# Shield.net
KiCad netlist of a schematic drawn in EAGLE
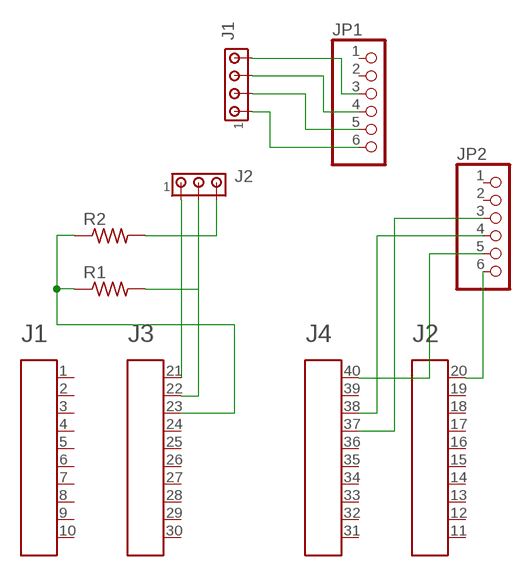
[diagram p0: schematic, sheet 1]

(export (version "E")
  (design (tool "Eeschema 10.0.6"))
  (components
    (comp (ref "A1")
      (value "HEADER4X10-BOOSTERPACK")
      (footprint "eagle-import:4X10-BOOSTERPACK")
      (libsource (lib "eagle-import") (part "HEADER4X10-BOOSTERPACK"))
    )
    (comp (ref "J1")
      (value "MTA04-156")
      (footprint "eagle-import:1X4MTA")
      (libsource (lib "eagle-import") (part "MTA04-156"))
    )
    (comp (ref "J2")
      (value "MTA03-156")
      (footprint "eagle-import:1X3MTA")
      (libsource (lib "eagle-import") (part "MTA03-156"))
    )
    (comp (ref "JP1")
      (value "PINHD-1X6")
      (footprint "eagle-import:1X06")
      (libsource (lib "eagle-import") (part "PINHD-1X6"))
    )
    (comp (ref "JP2")
      (value "PINHD-1X6")
      (footprint "eagle-import:1X06")
      (libsource (lib "eagle-import") (part "PINHD-1X6"))
    )
    (comp (ref "R1")
      (value "R-US_0207/10")
      (footprint "eagle-import:0207_10")
      (libsource (lib "eagle-import") (part "R-US_0207/10"))
    )
    (comp (ref "R2")
      (value "R-US_0207/10")
      (footprint "eagle-import:0207_10")
      (libsource (lib "eagle-import") (part "R-US_0207/10"))
    )
  )
  (nets
    (net (code "1") (name "Net-(A1-P$20)") (class "Default")
      (node (ref "A1") (pin "20") (pinfunction "P$20_20") (pintype "bidirectional"))
      (node (ref "JP2") (pin "6") (pinfunction "6_6") (pintype "passive"))
    )
    (net (code "2") (name "Net-(A1-P$21)") (class "Default")
      (node (ref "A1") (pin "21") (pinfunction "P$21_21") (pintype "bidirectional"))
      (node (ref "J2") (pin "1") (pinfunction "1_1") (pintype "passive"))
    )
    (net (code "3") (name "Net-(A1-P$22)") (class "Default")
      (node (ref "A1") (pin "22") (pinfunction "P$22_22") (pintype "bidirectional"))
      (node (ref "J2") (pin "2") (pinfunction "2_2") (pintype "passive"))
      (node (ref "R1") (pin "2") (pinfunction "2_2") (pintype "passive"))
    )
    (net (code "4") (name "Net-(A1-P$23)") (class "Default")
      (node (ref "A1") (pin "23") (pinfunction "P$23_23") (pintype "bidirectional"))
      (node (ref "R1") (pin "1") (pinfunction "1_1") (pintype "passive"))
      (node (ref "R2") (pin "1") (pinfunction "1_1") (pintype "passive"))
    )
    (net (code "5") (name "Net-(A1-P$37)") (class "Default")
      (node (ref "A1") (pin "37") (pinfunction "P$37_37") (pintype "bidirectional"))
      (node (ref "JP2") (pin "3") (pinfunction "3_3") (pintype "passive"))
    )
    (net (code "6") (name "Net-(A1-P$38)") (class "Default")
      (node (ref "A1") (pin "38") (pinfunction "P$38_38") (pintype "bidirectional"))
      (node (ref "JP2") (pin "4") (pinfunction "4_4") (pintype "passive"))
    )
    (net (code "7") (name "Net-(A1-P$40)") (class "Default")
      (node (ref "A1") (pin "40") (pinfunction "P$40_40") (pintype "bidirectional"))
      (node (ref "JP2") (pin "5") (pinfunction "5_5") (pintype "passive"))
    )
    (net (code "8") (name "Net-(J1-Pad1)") (class "Default")
      (node (ref "J1") (pin "1") (pinfunction "1_1") (pintype "passive"))
      (node (ref "JP1") (pin "6") (pinfunction "6_6") (pintype "passive"))
    )
    (net (code "9") (name "Net-(J1-Pad2)") (class "Default")
      (node (ref "J1") (pin "2") (pinfunction "2_2") (pintype "passive"))
      (node (ref "JP1") (pin "5") (pinfunction "5_5") (pintype "passive"))
    )
    (net (code "10") (name "Net-(J1-Pad3)") (class "Default")
      (node (ref "J1") (pin "3") (pinfunction "3_3") (pintype "passive"))
      (node (ref "JP1") (pin "4") (pinfunction "4_4") (pintype "passive"))
    )
    (net (code "11") (name "Net-(J1-Pad4)") (class "Default")
      (node (ref "J1") (pin "4") (pinfunction "4_4") (pintype "passive"))
      (node (ref "JP1") (pin "3") (pinfunction "3_3") (pintype "passive"))
    )
    (net (code "12") (name "Net-(J2-Pad3)") (class "Default")
      (node (ref "J2") (pin "3") (pinfunction "3_3") (pintype "passive"))
      (node (ref "R2") (pin "2") (pinfunction "2_2") (pintype "passive"))
    )
    (net (code "13") (name "unconnected-(A1-P$1-Pad1)") (class "Default")
      (node (ref "A1") (pin "1") (pinfunction "P$1_1") (pintype "bidirectional"))
    )
    (net (code "14") (name "unconnected-(A1-P$2-Pad2)") (class "Default")
      (node (ref "A1") (pin "2") (pinfunction "P$2_2") (pintype "bidirectional"))
    )
    (net (code "15") (name "unconnected-(A1-P$3-Pad3)") (class "Default")
      (node (ref "A1") (pin "3") (pinfunction "P$3_3") (pintype "bidirectional"))
    )
    (net (code "16") (name "unconnected-(A1-P$4-Pad4)") (class "Default")
      (node (ref "A1") (pin "4") (pinfunction "P$4_4") (pintype "bidirectional"))
    )
    (net (code "17") (name "unconnected-(A1-P$5-Pad5)") (class "Default")
      (node (ref "A1") (pin "5") (pinfunction "P$5_5") (pintype "bidirectional"))
    )
    (net (code "18") (name "unconnected-(A1-P$6-Pad6)") (class "Default")
      (node (ref "A1") (pin "6") (pinfunction "P$6_6") (pintype "bidirectional"))
    )
    (net (code "19") (name "unconnected-(A1-P$7-Pad7)") (class "Default")
      (node (ref "A1") (pin "7") (pinfunction "P$7_7") (pintype "bidirectional"))
    )
    (net (code "20") (name "unconnected-(A1-P$8-Pad8)") (class "Default")
      (node (ref "A1") (pin "8") (pinfunction "P$8_8") (pintype "bidirectional"))
    )
    (net (code "21") (name "unconnected-(A1-P$9-Pad9)") (class "Default")
      (node (ref "A1") (pin "9") (pinfunction "P$9_9") (pintype "bidirectional"))
    )
    (net (code "22") (name "unconnected-(A1-P$10-Pad10)") (class "Default")
      (node (ref "A1") (pin "10") (pinfunction "P$10_10") (pintype "bidirectional"))
    )
    (net (code "23") (name "unconnected-(A1-P$11-Pad11)") (class "Default")
      (node (ref "A1") (pin "11") (pinfunction "P$11_11") (pintype "bidirectional"))
    )
    (net (code "24") (name "unconnected-(A1-P$12-Pad12)") (class "Default")
      (node (ref "A1") (pin "12") (pinfunction "P$12_12") (pintype "bidirectional"))
    )
    (net (code "25") (name "unconnected-(A1-P$13-Pad13)") (class "Default")
      (node (ref "A1") (pin "13") (pinfunction "P$13_13") (pintype "bidirectional"))
    )
    (net (code "26") (name "unconnected-(A1-P$14-Pad14)") (class "Default")
      (node (ref "A1") (pin "14") (pinfunction "P$14_14") (pintype "bidirectional"))
    )
    (net (code "27") (name "unconnected-(A1-P$15-Pad15)") (class "Default")
      (node (ref "A1") (pin "15") (pinfunction "P$15_15") (pintype "bidirectional"))
    )
    (net (code "28") (name "unconnected-(A1-P$16-Pad16)") (class "Default")
      (node (ref "A1") (pin "16") (pinfunction "P$16_16") (pintype "bidirectional"))
    )
    (net (code "29") (name "unconnected-(A1-P$17-Pad17)") (class "Default")
      (node (ref "A1") (pin "17") (pinfunction "P$17_17") (pintype "bidirectional"))
    )
    (net (code "30") (name "unconnected-(A1-P$18-Pad18)") (class "Default")
      (node (ref "A1") (pin "18") (pinfunction "P$18_18") (pintype "bidirectional"))
    )
    (net (code "31") (name "unconnected-(A1-P$19-Pad19)") (class "Default")
      (node (ref "A1") (pin "19") (pinfunction "P$19_19") (pintype "bidirectional"))
    )
    (net (code "32") (name "unconnected-(A1-P$24-Pad24)") (class "Default")
      (node (ref "A1") (pin "24") (pinfunction "P$24_24") (pintype "bidirectional"))
    )
    (net (code "33") (name "unconnected-(A1-P$25-Pad25)") (class "Default")
      (node (ref "A1") (pin "25") (pinfunction "P$25_25") (pintype "bidirectional"))
    )
    (net (code "34") (name "unconnected-(A1-P$26-Pad26)") (class "Default")
      (node (ref "A1") (pin "26") (pinfunction "P$26_26") (pintype "bidirectional"))
    )
    (net (code "35") (name "unconnected-(A1-P$27-Pad27)") (class "Default")
      (node (ref "A1") (pin "27") (pinfunction "P$27_27") (pintype "bidirectional"))
    )
    (net (code "36") (name "unconnected-(A1-P$28-Pad28)") (class "Default")
      (node (ref "A1") (pin "28") (pinfunction "P$28_28") (pintype "bidirectional"))
    )
    (net (code "37") (name "unconnected-(A1-P$29-Pad29)") (class "Default")
      (node (ref "A1") (pin "29") (pinfunction "P$29_29") (pintype "bidirectional"))
    )
    (net (code "38") (name "unconnected-(A1-P$30-Pad30)") (class "Default")
      (node (ref "A1") (pin "30") (pinfunction "P$30_30") (pintype "bidirectional"))
    )
    (net (code "39") (name "unconnected-(A1-P$31-Pad31)") (class "Default")
      (node (ref "A1") (pin "31") (pinfunction "P$31_31") (pintype "bidirectional"))
    )
    (net (code "40") (name "unconnected-(A1-P$32-Pad32)") (class "Default")
      (node (ref "A1") (pin "32") (pinfunction "P$32_32") (pintype "bidirectional"))
    )
    (net (code "41") (name "unconnected-(A1-P$33-Pad33)") (class "Default")
      (node (ref "A1") (pin "33") (pinfunction "P$33_33") (pintype "bidirectional"))
    )
    (net (code "42") (name "unconnected-(A1-P$34-Pad34)") (class "Default")
      (node (ref "A1") (pin "34") (pinfunction "P$34_34") (pintype "bidirectional"))
    )
    (net (code "43") (name "unconnected-(A1-P$35-Pad35)") (class "Default")
      (node (ref "A1") (pin "35") (pinfunction "P$35_35") (pintype "bidirectional"))
    )
    (net (code "44") (name "unconnected-(A1-P$36-Pad36)") (class "Default")
      (node (ref "A1") (pin "36") (pinfunction "P$36_36") (pintype "bidirectional"))
    )
    (net (code "45") (name "unconnected-(A1-P$39-Pad39)") (class "Default")
      (node (ref "A1") (pin "39") (pinfunction "P$39_39") (pintype "bidirectional"))
    )
    (net (code "46") (name "unconnected-(JP1-Pad1)") (class "Default")
      (node (ref "JP1") (pin "1") (pinfunction "1_1") (pintype "passive"))
    )
    (net (code "47") (name "unconnected-(JP1-Pad2)") (class "Default")
      (node (ref "JP1") (pin "2") (pinfunction "2_2") (pintype "passive"))
    )
    (net (code "48") (name "unconnected-(JP2-Pad1)") (class "Default")
      (node (ref "JP2") (pin "1") (pinfunction "1_1") (pintype "passive"))
    )
    (net (code "49") (name "unconnected-(JP2-Pad2)") (class "Default")
      (node (ref "JP2") (pin "2") (pinfunction "2_2") (pintype "passive"))
    )
  )
)
